# TOP_BEE_DEMO.net
KiCad netlist of a schematic drawn in EAGLE
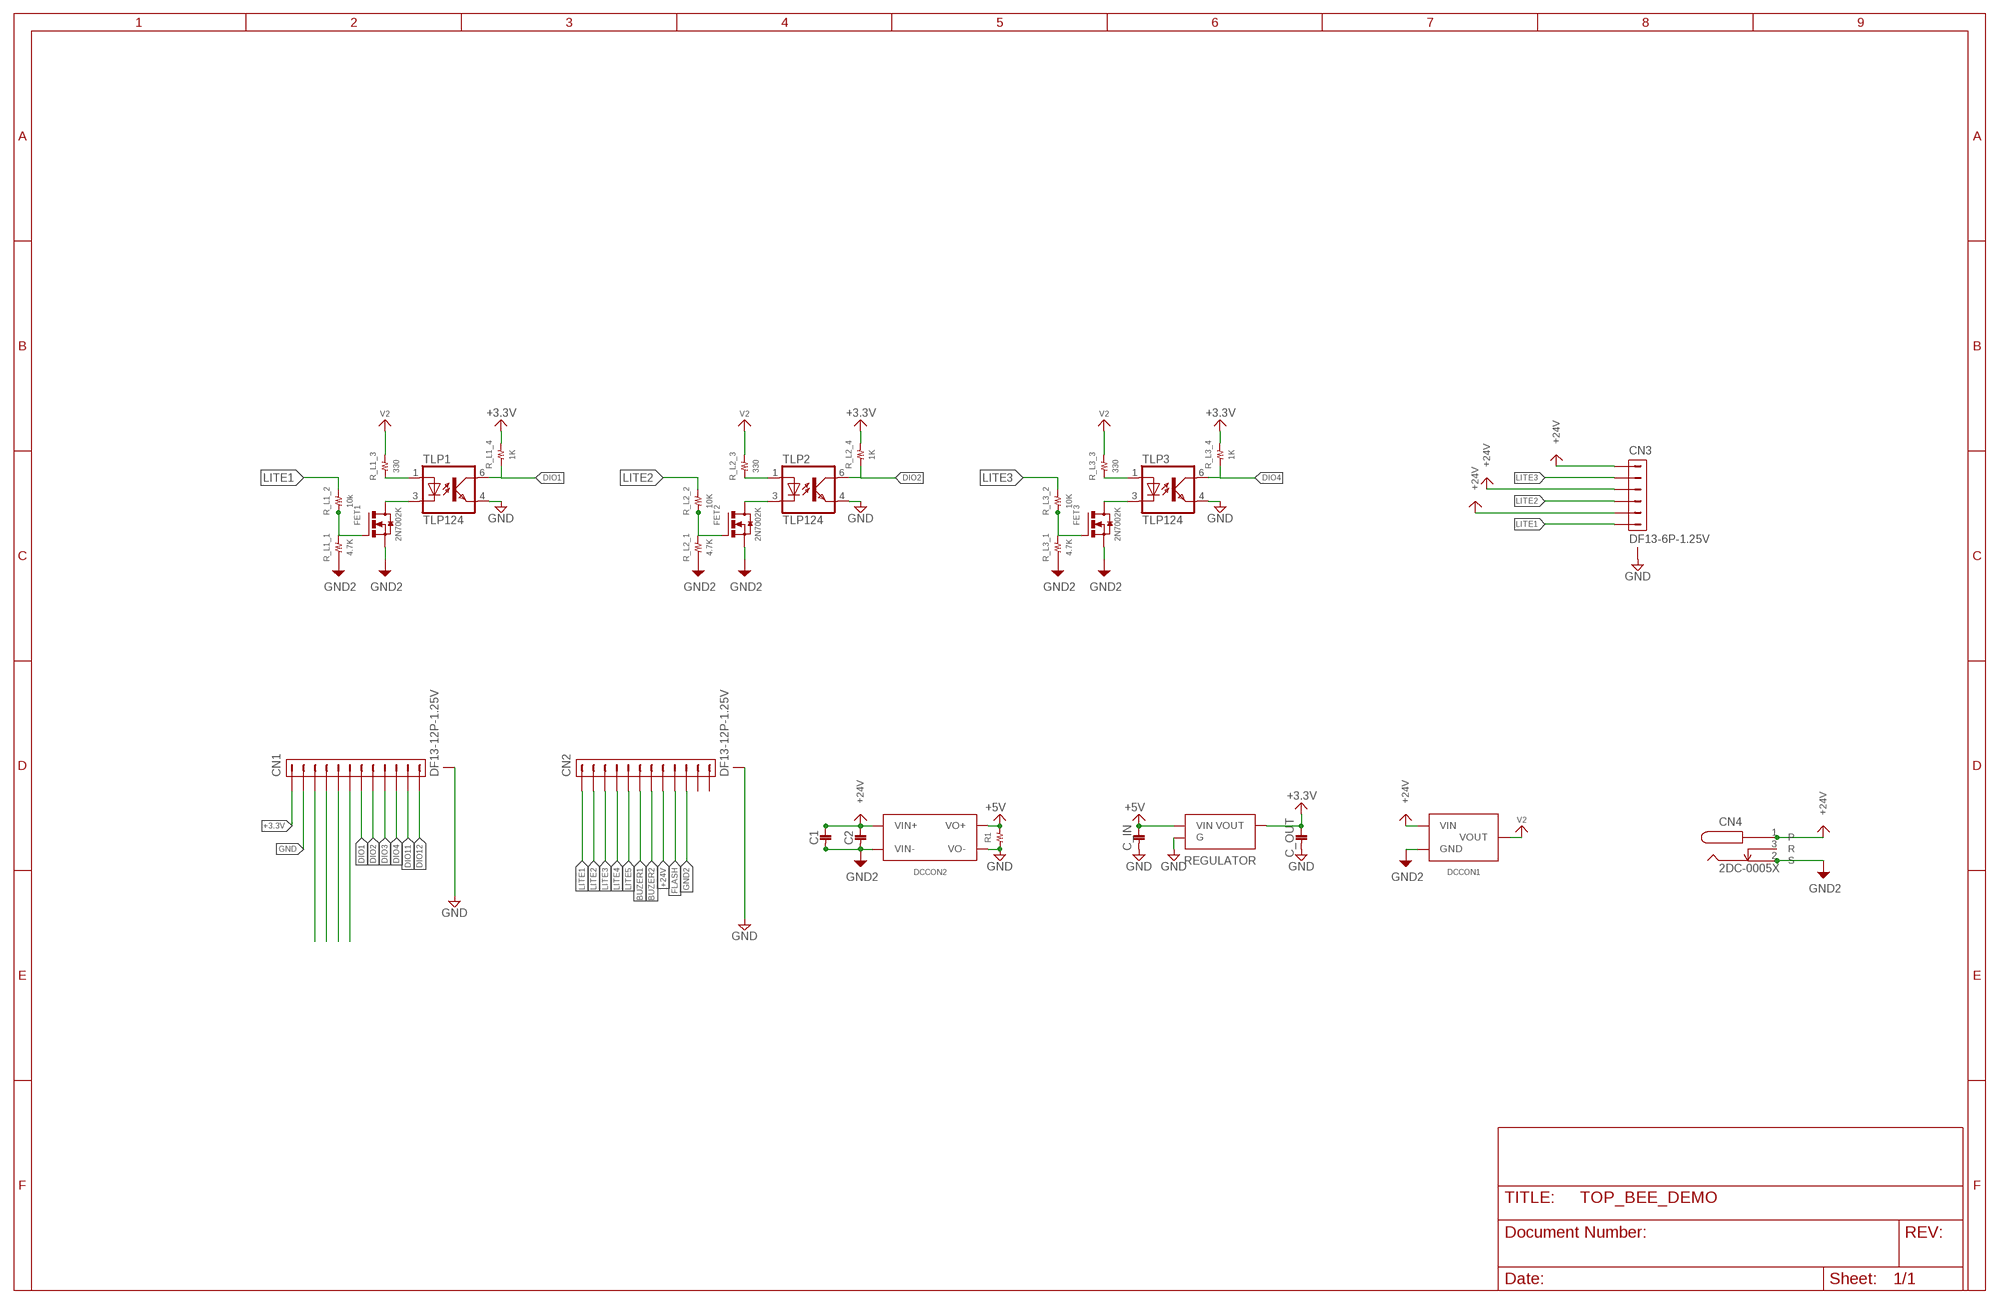
[diagram p0: schematic, sheet 1]

(export (version "E")
  (design (tool "Eeschema 10.0.6"))
  (components
    (comp (ref "C1")
      (value "3225")
      (footprint "eagle-import:3225")
      (libsource (lib "eagle-import") (part "3225"))
    )
    (comp (ref "C2")
      (value "1608")
      (footprint "eagle-import:1608")
      (libsource (lib "eagle-import") (part "1608"))
    )
    (comp (ref "CN1")
      (value "DF13-12P-1.25V")
      (footprint "eagle-import:DF13C-12P-1.25V")
      (libsource (lib "eagle-import") (part "DF13-12P-1.25V"))
    )
    (comp (ref "CN2")
      (value "DF13-12P-1.25V")
      (footprint "eagle-import:DF13C-12P-1.25V")
      (libsource (lib "eagle-import") (part "DF13-12P-1.25V"))
    )
    (comp (ref "CN3")
      (value "DF13-6P-1.25V")
      (footprint "eagle-import:DF13C-6P-1.25V")
      (libsource (lib "eagle-import") (part "DF13-6P-1.25V"))
    )
    (comp (ref "CN4")
      (value "2DC-0005X")
      (footprint "eagle-import:2DC-0005D")
      (libsource (lib "eagle-import") (part "2DC-0005X"))
    )
    (comp (ref "C_IN")
      (value "1608")
      (footprint "eagle-import:1608")
      (libsource (lib "eagle-import") (part "1608"))
    )
    (comp (ref "C_OUT")
      (value "1608")
      (footprint "eagle-import:1608")
      (libsource (lib "eagle-import") (part "1608"))
    )
    (comp (ref "DCCON1")
      (value "Ｒ－７８Ｅ５．０")
      (footprint "eagle-import:Ｒ－７８Ｅ５．０")
      (libsource (lib "eagle-import") (part "Ｒ－７８Ｅ５．０"))
    )
    (comp (ref "DCCON2")
      (value "MAU100")
      (footprint "eagle-import:MAU")
      (libsource (lib "eagle-import") (part "MAU100"))
    )
    (comp (ref "FET1")
      (value "2N7002K")
      (footprint "eagle-import:SOT23")
      (libsource (lib "eagle-import") (part "CHIP_FET"))
    )
    (comp (ref "FET2")
      (value "2N7002K")
      (footprint "eagle-import:SOT23")
      (libsource (lib "eagle-import") (part "CHIP_FET"))
    )
    (comp (ref "FET3")
      (value "2N7002K")
      (footprint "eagle-import:SOT23")
      (libsource (lib "eagle-import") (part "CHIP_FET"))
    )
    (comp (ref "R1")
      (value "RESISTOR__SMD")
      (footprint "eagle-import:1608")
      (libsource (lib "eagle-import") (part "RESISTOR__SMD"))
    )
    (comp (ref "REGULATOR")
      (value "NJM2845")
      (footprint "eagle-import:TO252")
      (libsource (lib "eagle-import") (part "NJM2845"))
    )
    (comp (ref "R_L1_1")
      (value "4.7K")
      (footprint "eagle-import:1608")
      (libsource (lib "eagle-import") (part "RESISTOR__SMD"))
    )
    (comp (ref "R_L1_2")
      (value "10k")
      (footprint "eagle-import:1608")
      (libsource (lib "eagle-import") (part "RESISTOR__SMD"))
    )
    (comp (ref "R_L1_3")
      (value "330")
      (footprint "eagle-import:1608")
      (libsource (lib "eagle-import") (part "RESISTOR__SMD"))
    )
    (comp (ref "R_L1_4")
      (value "1K")
      (footprint "eagle-import:1608")
      (libsource (lib "eagle-import") (part "RESISTOR__SMD"))
    )
    (comp (ref "R_L2_1")
      (value "4.7K")
      (footprint "eagle-import:1608")
      (libsource (lib "eagle-import") (part "RESISTOR__SMD"))
    )
    (comp (ref "R_L2_2")
      (value "10K")
      (footprint "eagle-import:1608")
      (libsource (lib "eagle-import") (part "RESISTOR__SMD"))
    )
    (comp (ref "R_L2_3")
      (value "330")
      (footprint "eagle-import:1608")
      (libsource (lib "eagle-import") (part "RESISTOR__SMD"))
    )
    (comp (ref "R_L2_4")
      (value "1K")
      (footprint "eagle-import:1608")
      (libsource (lib "eagle-import") (part "RESISTOR__SMD"))
    )
    (comp (ref "R_L3_1")
      (value "4.7K")
      (footprint "eagle-import:1608")
      (libsource (lib "eagle-import") (part "RESISTOR__SMD"))
    )
    (comp (ref "R_L3_2")
      (value "10K")
      (footprint "eagle-import:1608")
      (libsource (lib "eagle-import") (part "RESISTOR__SMD"))
    )
    (comp (ref "R_L3_3")
      (value "330")
      (footprint "eagle-import:1608")
      (libsource (lib "eagle-import") (part "RESISTOR__SMD"))
    )
    (comp (ref "R_L3_4")
      (value "1K")
      (footprint "eagle-import:1608")
      (libsource (lib "eagle-import") (part "RESISTOR__SMD"))
    )
    (comp (ref "TLP1")
      (value "TLP124")
      (footprint "eagle-import:11−4C1")
      (libsource (lib "eagle-import") (part "TLP124"))
    )
    (comp (ref "TLP2")
      (value "TLP124")
      (footprint "eagle-import:11−4C1")
      (libsource (lib "eagle-import") (part "TLP124"))
    )
    (comp (ref "TLP3")
      (value "TLP124")
      (footprint "eagle-import:11−4C1")
      (libsource (lib "eagle-import") (part "TLP124"))
    )
  )
  (nets
    (net (code "1") (name "+3.3V") (class "Default")
      (node (ref "CN1") (pin "P$1") (pinfunction "1_P$1") (pintype "passive"))
      (node (ref "C_OUT") (pin "P$1") (pinfunction "1_P$1") (pintype "passive"))
      (node (ref "REGULATOR") (pin "3") (pinfunction "VOUT_3") (pintype "power_in"))
      (node (ref "R_L1_4") (pin "2") (pinfunction "P$2_2") (pintype "passive"))
      (node (ref "R_L2_4") (pin "2") (pinfunction "P$2_2") (pintype "passive"))
      (node (ref "R_L3_4") (pin "2") (pinfunction "P$2_2") (pintype "passive"))
    )
    (net (code "2") (name "+5V") (class "Default")
      (node (ref "C_IN") (pin "P$1") (pinfunction "1_P$1") (pintype "passive"))
      (node (ref "DCCON2") (pin "P$5") (pinfunction "VO+_P$5") (pintype "bidirectional"))
      (node (ref "R1") (pin "2") (pinfunction "P$2_2") (pintype "passive"))
      (node (ref "REGULATOR") (pin "1") (pinfunction "VIN_1") (pintype "power_in"))
    )
    (net (code "3") (name "+24V") (class "Default")
      (node (ref "C1") (pin "P$1") (pinfunction "1_P$1") (pintype "passive"))
      (node (ref "C2") (pin "P$1") (pinfunction "1_P$1") (pintype "passive"))
      (node (ref "CN2") (pin "P$8") (pinfunction "8_P$8") (pintype "passive"))
      (node (ref "CN3") (pin "P$1") (pinfunction "1_P$1") (pintype "passive"))
      (node (ref "CN3") (pin "P$3") (pinfunction "3_P$3") (pintype "passive"))
      (node (ref "CN3") (pin "P$5") (pinfunction "5_P$5") (pintype "passive"))
      (node (ref "CN4") (pin "1") (pinfunction "P_1") (pintype "power_in"))
      (node (ref "DCCON1") (pin "1") (pinfunction "VIN_1") (pintype "bidirectional"))
      (node (ref "DCCON2") (pin "P$1") (pinfunction "VIN+_P$1") (pintype "bidirectional"))
    )
    (net (code "4") (name "BUZER1") (class "Default")
      (node (ref "CN2") (pin "P$6") (pinfunction "6_P$6") (pintype "passive"))
    )
    (net (code "5") (name "BUZER2") (class "Default")
      (node (ref "CN2") (pin "P$7") (pinfunction "7_P$7") (pintype "passive"))
    )
    (net (code "6") (name "DIO1") (class "Default")
      (node (ref "CN1") (pin "P$7") (pinfunction "7_P$7") (pintype "passive"))
      (node (ref "R_L1_4") (pin "1") (pinfunction "P$1_1") (pintype "passive"))
      (node (ref "TLP1") (pin "6") (pinfunction "COL_6") (pintype "passive"))
    )
    (net (code "7") (name "DIO2") (class "Default")
      (node (ref "CN1") (pin "P$8") (pinfunction "8_P$8") (pintype "passive"))
      (node (ref "R_L2_4") (pin "1") (pinfunction "P$1_1") (pintype "passive"))
      (node (ref "TLP2") (pin "6") (pinfunction "COL_6") (pintype "passive"))
    )
    (net (code "8") (name "DIO3") (class "Default")
      (node (ref "CN1") (pin "P$9") (pinfunction "9_P$9") (pintype "passive"))
    )
    (net (code "9") (name "DIO4") (class "Default")
      (node (ref "CN1") (pin "P$10") (pinfunction "10_P$10") (pintype "passive"))
      (node (ref "R_L3_4") (pin "1") (pinfunction "P$1_1") (pintype "passive"))
      (node (ref "TLP3") (pin "6") (pinfunction "COL_6") (pintype "passive"))
    )
    (net (code "10") (name "DIO11") (class "Default")
      (node (ref "CN1") (pin "P$11") (pinfunction "11_P$11") (pintype "passive"))
    )
    (net (code "11") (name "DIO12") (class "Default")
      (node (ref "CN1") (pin "P$12") (pinfunction "12_P$12") (pintype "passive"))
    )
    (net (code "12") (name "FLASH") (class "Default")
      (node (ref "CN2") (pin "P$9") (pinfunction "9_P$9") (pintype "passive"))
    )
    (net (code "13") (name "GND") (class "Default")
      (node (ref "CN1") (pin "G1") (pinfunction "G_G1") (pintype "bidirectional"))
      (node (ref "CN1") (pin "G2") (pinfunction "G_G2") (pintype "bidirectional"))
      (node (ref "CN1") (pin "M$0") (pinfunction "G_M$0") (pintype "bidirectional"))
      (node (ref "CN1") (pin "M$1") (pinfunction "G_M$1") (pintype "bidirectional"))
      (node (ref "CN1") (pin "P$2") (pinfunction "2_P$2") (pintype "passive"))
      (node (ref "CN2") (pin "G1") (pinfunction "G_G1") (pintype "bidirectional"))
      (node (ref "CN2") (pin "G2") (pinfunction "G_G2") (pintype "bidirectional"))
      (node (ref "CN2") (pin "M$0") (pinfunction "G_M$0") (pintype "bidirectional"))
      (node (ref "CN2") (pin "M$1") (pinfunction "G_M$1") (pintype "bidirectional"))
      (node (ref "CN3") (pin "G1") (pinfunction "G_G1") (pintype "bidirectional"))
      (node (ref "CN3") (pin "G2") (pinfunction "G_G2") (pintype "bidirectional"))
      (node (ref "CN3") (pin "M$0") (pinfunction "G_M$0") (pintype "bidirectional"))
      (node (ref "CN3") (pin "M$1") (pinfunction "G_M$1") (pintype "bidirectional"))
      (node (ref "C_IN") (pin "P$2") (pinfunction "2_P$2") (pintype "passive"))
      (node (ref "C_OUT") (pin "P$2") (pinfunction "2_P$2") (pintype "passive"))
      (node (ref "DCCON2") (pin "P$3") (pinfunction "VO-_P$3") (pintype "bidirectional"))
      (node (ref "R1") (pin "1") (pinfunction "P$1_1") (pintype "passive"))
      (node (ref "REGULATOR") (pin "2") (pinfunction "G_2") (pintype "power_in"))
      (node (ref "TLP1") (pin "4") (pinfunction "EMIT_4") (pintype "passive"))
      (node (ref "TLP2") (pin "4") (pinfunction "EMIT_4") (pintype "passive"))
      (node (ref "TLP3") (pin "4") (pinfunction "EMIT_4") (pintype "passive"))
    )
    (net (code "14") (name "GND2") (class "Default")
      (node (ref "C1") (pin "P$2") (pinfunction "2_P$2") (pintype "passive"))
      (node (ref "C2") (pin "P$2") (pinfunction "2_P$2") (pintype "passive"))
      (node (ref "CN2") (pin "P$10") (pinfunction "10_P$10") (pintype "passive"))
      (node (ref "CN4") (pin "2") (pinfunction "S_2") (pintype "power_in"))
      (node (ref "DCCON1") (pin "2") (pinfunction "GND_2") (pintype "bidirectional"))
      (node (ref "DCCON2") (pin "P$2") (pinfunction "VIN-_P$2") (pintype "bidirectional"))
      (node (ref "FET1") (pin "2") (pinfunction "S_2") (pintype "passive"))
      (node (ref "FET2") (pin "2") (pinfunction "S_2") (pintype "passive"))
      (node (ref "FET3") (pin "2") (pinfunction "S_2") (pintype "passive"))
      (node (ref "R_L1_1") (pin "1") (pinfunction "P$1_1") (pintype "passive"))
      (node (ref "R_L2_1") (pin "1") (pinfunction "P$1_1") (pintype "passive"))
      (node (ref "R_L3_1") (pin "1") (pinfunction "P$1_1") (pintype "passive"))
    )
    (net (code "15") (name "LITE1") (class "Default")
      (node (ref "CN2") (pin "P$1") (pinfunction "1_P$1") (pintype "passive"))
      (node (ref "CN3") (pin "P$6") (pinfunction "6_P$6") (pintype "passive"))
      (node (ref "R_L1_2") (pin "2") (pinfunction "P$2_2") (pintype "passive"))
    )
    (net (code "16") (name "LITE2") (class "Default")
      (node (ref "CN2") (pin "P$2") (pinfunction "2_P$2") (pintype "passive"))
      (node (ref "CN3") (pin "P$4") (pinfunction "4_P$4") (pintype "passive"))
      (node (ref "R_L2_2") (pin "2") (pinfunction "P$2_2") (pintype "passive"))
    )
    (net (code "17") (name "LITE3") (class "Default")
      (node (ref "CN2") (pin "P$3") (pinfunction "3_P$3") (pintype "passive"))
      (node (ref "CN3") (pin "P$2") (pinfunction "2_P$2") (pintype "passive"))
      (node (ref "R_L3_2") (pin "2") (pinfunction "P$2_2") (pintype "passive"))
    )
    (net (code "18") (name "LITE4") (class "Default")
      (node (ref "CN2") (pin "P$4") (pinfunction "4_P$4") (pintype "passive"))
    )
    (net (code "19") (name "LITE5") (class "Default")
      (node (ref "CN2") (pin "P$5") (pinfunction "5_P$5") (pintype "passive"))
    )
    (net (code "20") (name "Net-(FET1-D)") (class "Default")
      (node (ref "FET1") (pin "3") (pinfunction "D_3") (pintype "passive"))
      (node (ref "TLP1") (pin "3") (pinfunction "C_3") (pintype "passive"))
    )
    (net (code "21") (name "Net-(FET1-G)") (class "Default")
      (node (ref "FET1") (pin "1") (pinfunction "G_1") (pintype "passive"))
      (node (ref "R_L1_1") (pin "2") (pinfunction "P$2_2") (pintype "passive"))
      (node (ref "R_L1_2") (pin "1") (pinfunction "P$1_1") (pintype "passive"))
    )
    (net (code "22") (name "Net-(FET2-D)") (class "Default")
      (node (ref "FET2") (pin "3") (pinfunction "D_3") (pintype "passive"))
      (node (ref "TLP2") (pin "3") (pinfunction "C_3") (pintype "passive"))
    )
    (net (code "23") (name "Net-(FET2-G)") (class "Default")
      (node (ref "FET2") (pin "1") (pinfunction "G_1") (pintype "passive"))
      (node (ref "R_L2_1") (pin "2") (pinfunction "P$2_2") (pintype "passive"))
      (node (ref "R_L2_2") (pin "1") (pinfunction "P$1_1") (pintype "passive"))
    )
    (net (code "24") (name "Net-(FET3-D)") (class "Default")
      (node (ref "FET3") (pin "3") (pinfunction "D_3") (pintype "passive"))
      (node (ref "TLP3") (pin "3") (pinfunction "C_3") (pintype "passive"))
    )
    (net (code "25") (name "Net-(FET3-G)") (class "Default")
      (node (ref "FET3") (pin "1") (pinfunction "G_1") (pintype "passive"))
      (node (ref "R_L3_1") (pin "2") (pinfunction "P$2_2") (pintype "passive"))
      (node (ref "R_L3_2") (pin "1") (pinfunction "P$1_1") (pintype "passive"))
    )
    (net (code "26") (name "Net-(R_L1_3-P$1)") (class "Default")
      (node (ref "R_L1_3") (pin "1") (pinfunction "P$1_1") (pintype "passive"))
      (node (ref "TLP1") (pin "1") (pinfunction "A_1") (pintype "passive"))
    )
    (net (code "27") (name "Net-(R_L2_3-P$1)") (class "Default")
      (node (ref "R_L2_3") (pin "1") (pinfunction "P$1_1") (pintype "passive"))
      (node (ref "TLP2") (pin "1") (pinfunction "A_1") (pintype "passive"))
    )
    (net (code "28") (name "Net-(R_L3_3-P$1)") (class "Default")
      (node (ref "R_L3_3") (pin "1") (pinfunction "P$1_1") (pintype "passive"))
      (node (ref "TLP3") (pin "1") (pinfunction "A_1") (pintype "passive"))
    )
    (net (code "29") (name "V2") (class "Default")
      (node (ref "DCCON1") (pin "3") (pinfunction "VOUT_3") (pintype "bidirectional"))
      (node (ref "R_L1_3") (pin "2") (pinfunction "P$2_2") (pintype "passive"))
      (node (ref "R_L2_3") (pin "2") (pinfunction "P$2_2") (pintype "passive"))
      (node (ref "R_L3_3") (pin "2") (pinfunction "P$2_2") (pintype "passive"))
    )
    (net (code "30") (name "unconnected-(CN1-3-PadP$3)") (class "Default")
      (node (ref "CN1") (pin "P$3") (pinfunction "3_P$3") (pintype "passive"))
    )
    (net (code "31") (name "unconnected-(CN1-4-PadP$4)") (class "Default")
      (node (ref "CN1") (pin "P$4") (pinfunction "4_P$4") (pintype "passive"))
    )
    (net (code "32") (name "unconnected-(CN1-5-PadP$5)") (class "Default")
      (node (ref "CN1") (pin "P$5") (pinfunction "5_P$5") (pintype "passive"))
    )
    (net (code "33") (name "unconnected-(CN1-6-PadP$6)") (class "Default")
      (node (ref "CN1") (pin "P$6") (pinfunction "6_P$6") (pintype "passive"))
    )
    (net (code "34") (name "unconnected-(CN2-11-PadP$11)") (class "Default")
      (node (ref "CN2") (pin "P$11") (pinfunction "11_P$11") (pintype "passive"))
    )
    (net (code "35") (name "unconnected-(CN2-12-PadP$12)") (class "Default")
      (node (ref "CN2") (pin "P$12") (pinfunction "12_P$12") (pintype "passive"))
    )
    (net (code "36") (name "unconnected-(CN4-R-Pad3)") (class "Default")
      (node (ref "CN4") (pin "3") (pinfunction "R_3") (pintype "input"))
    )
  )
)
